# DCF77_RX_1V0.net
KiCad netlist of a schematic drawn in EAGLE
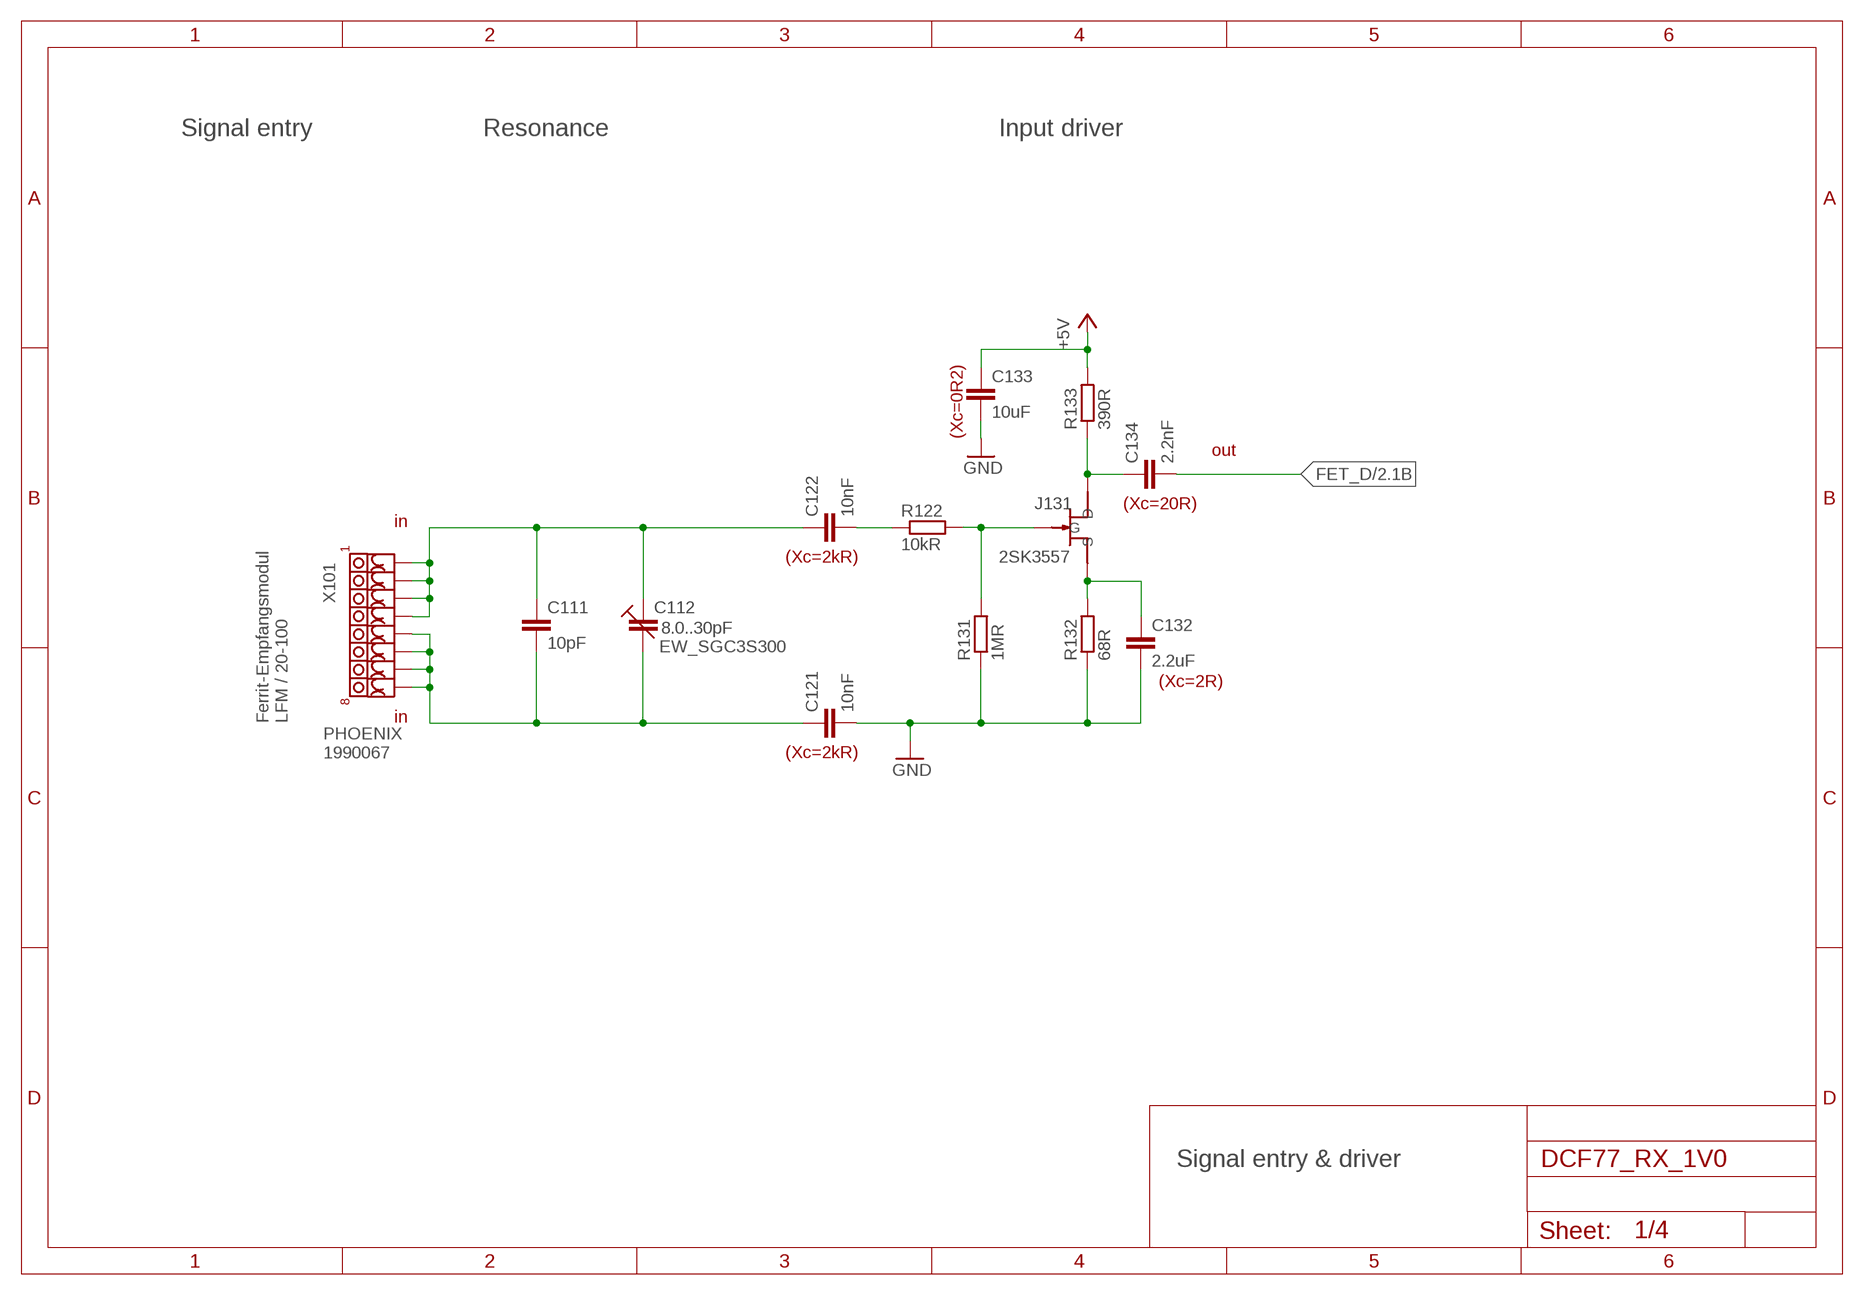
[diagram p0: schematic, sheet 1]
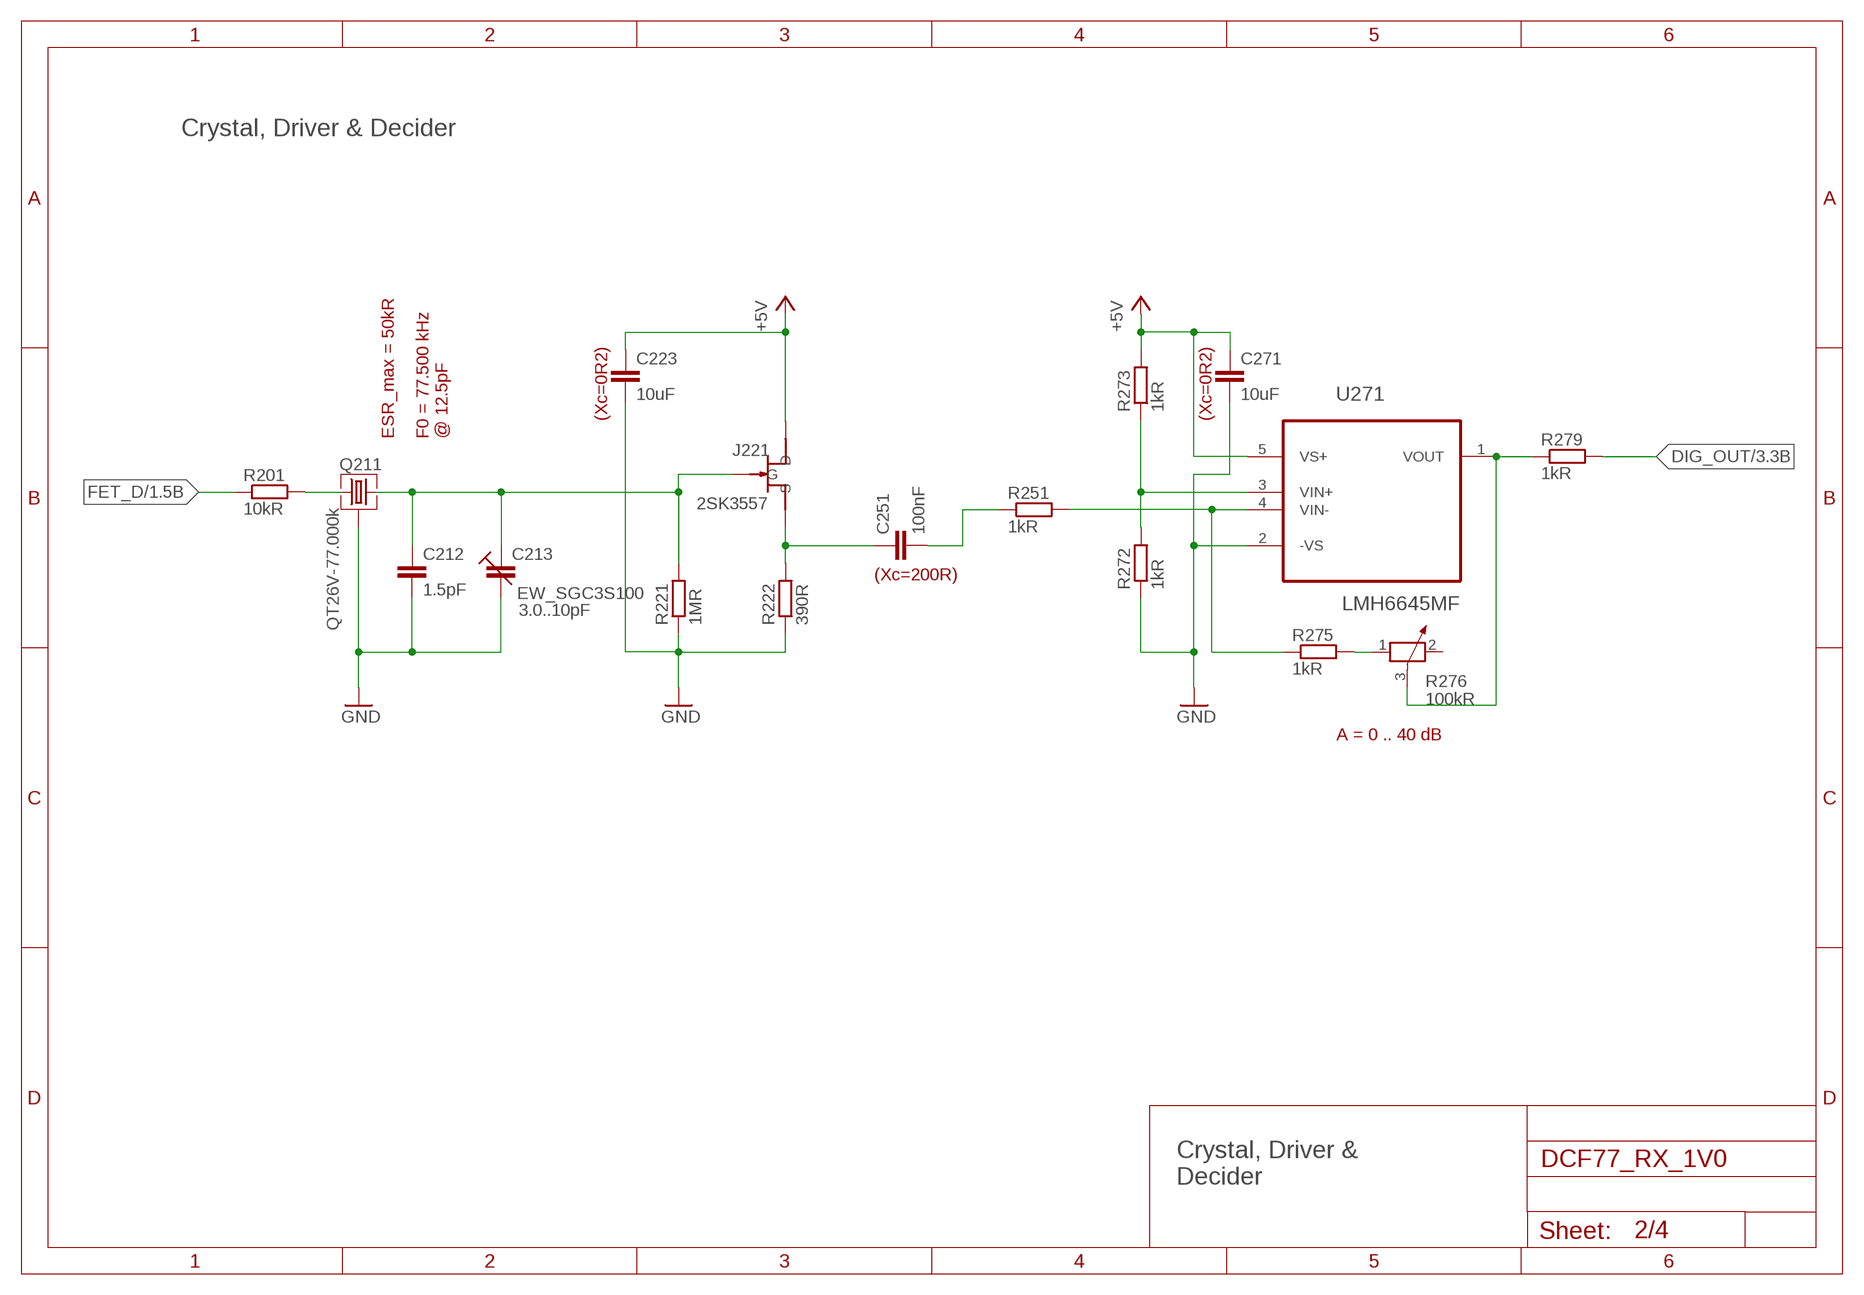
[diagram p1: schematic, sheet 2]
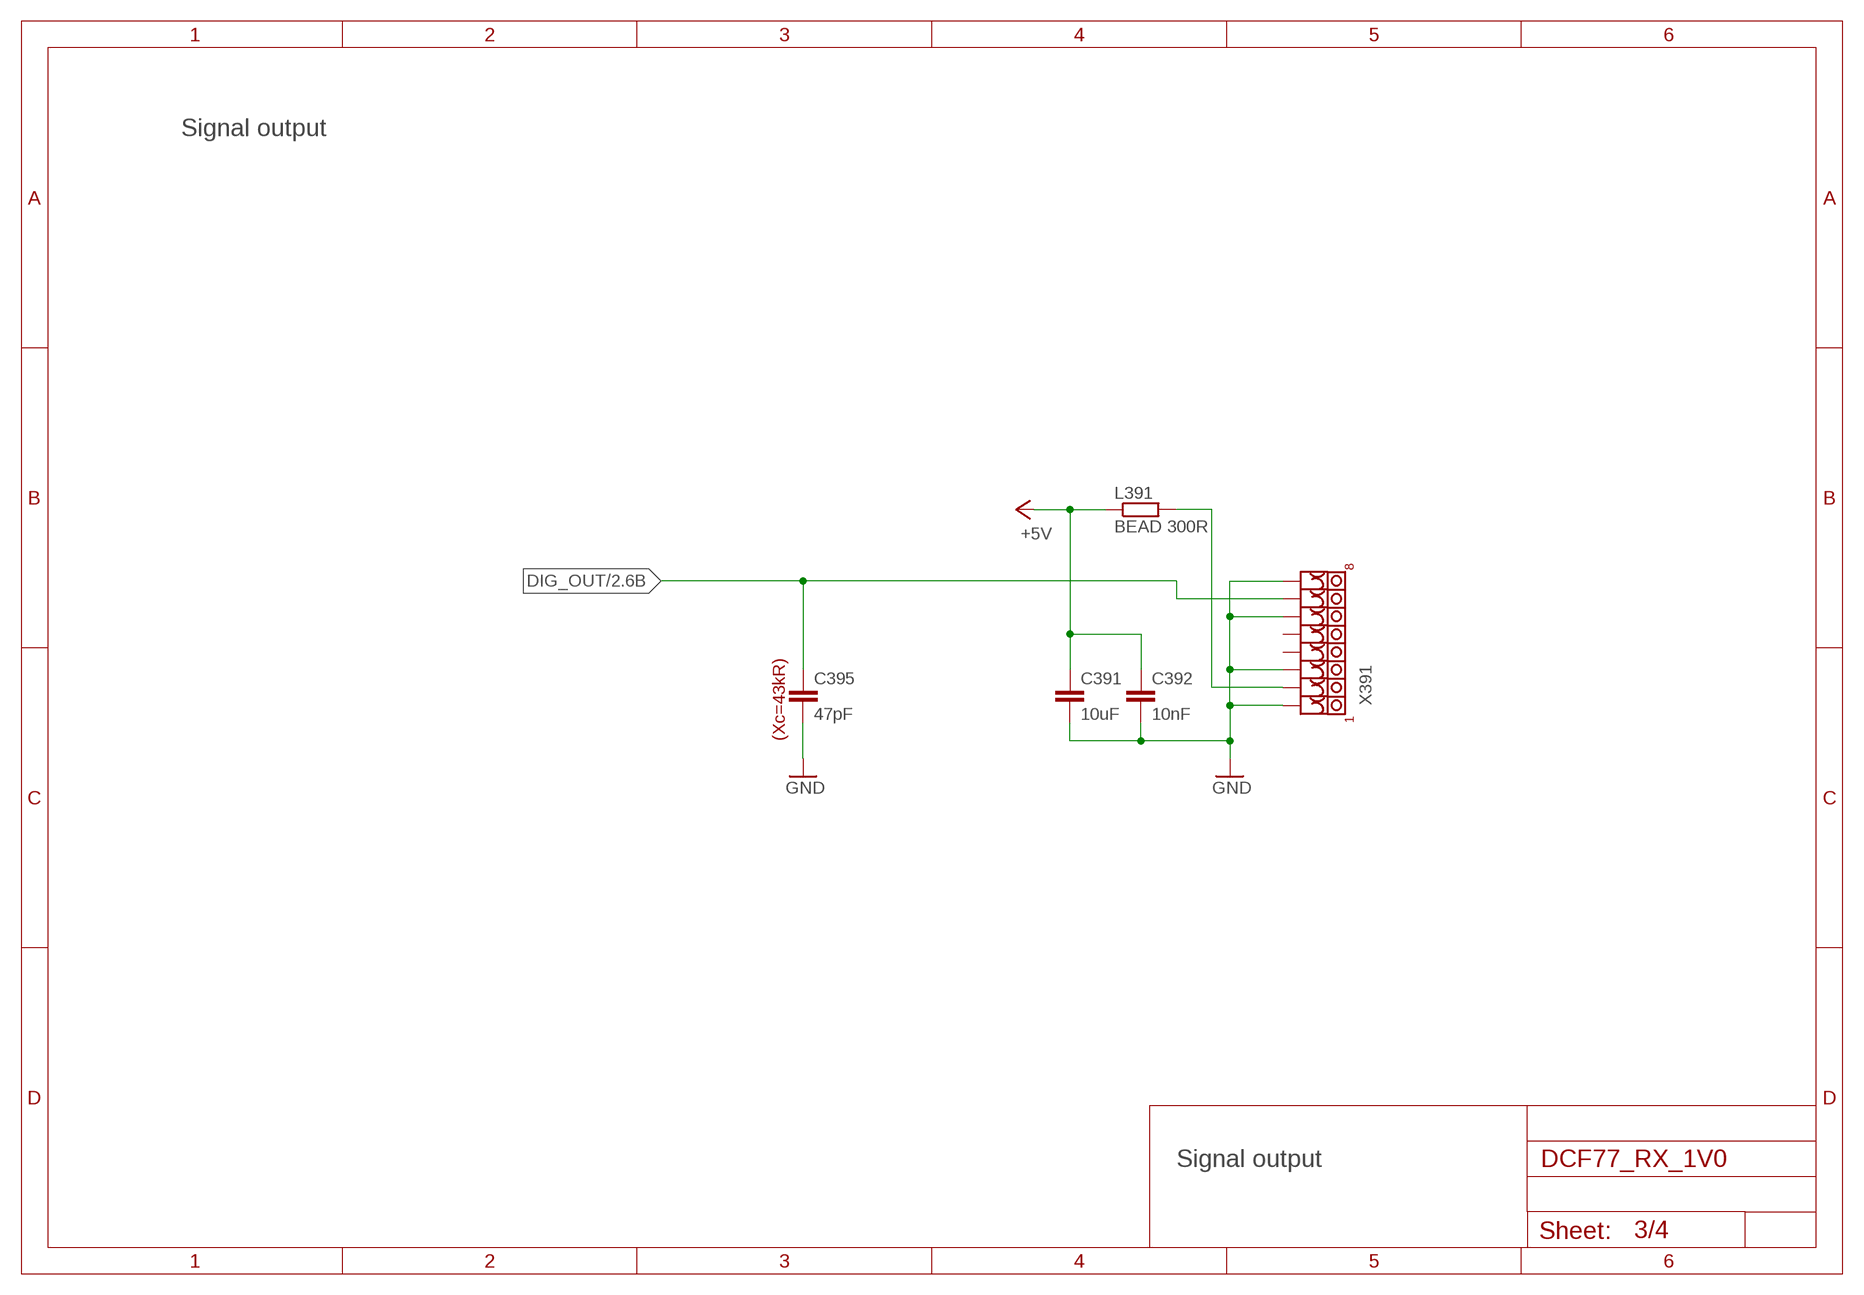
[diagram p2: schematic, sheet 3]
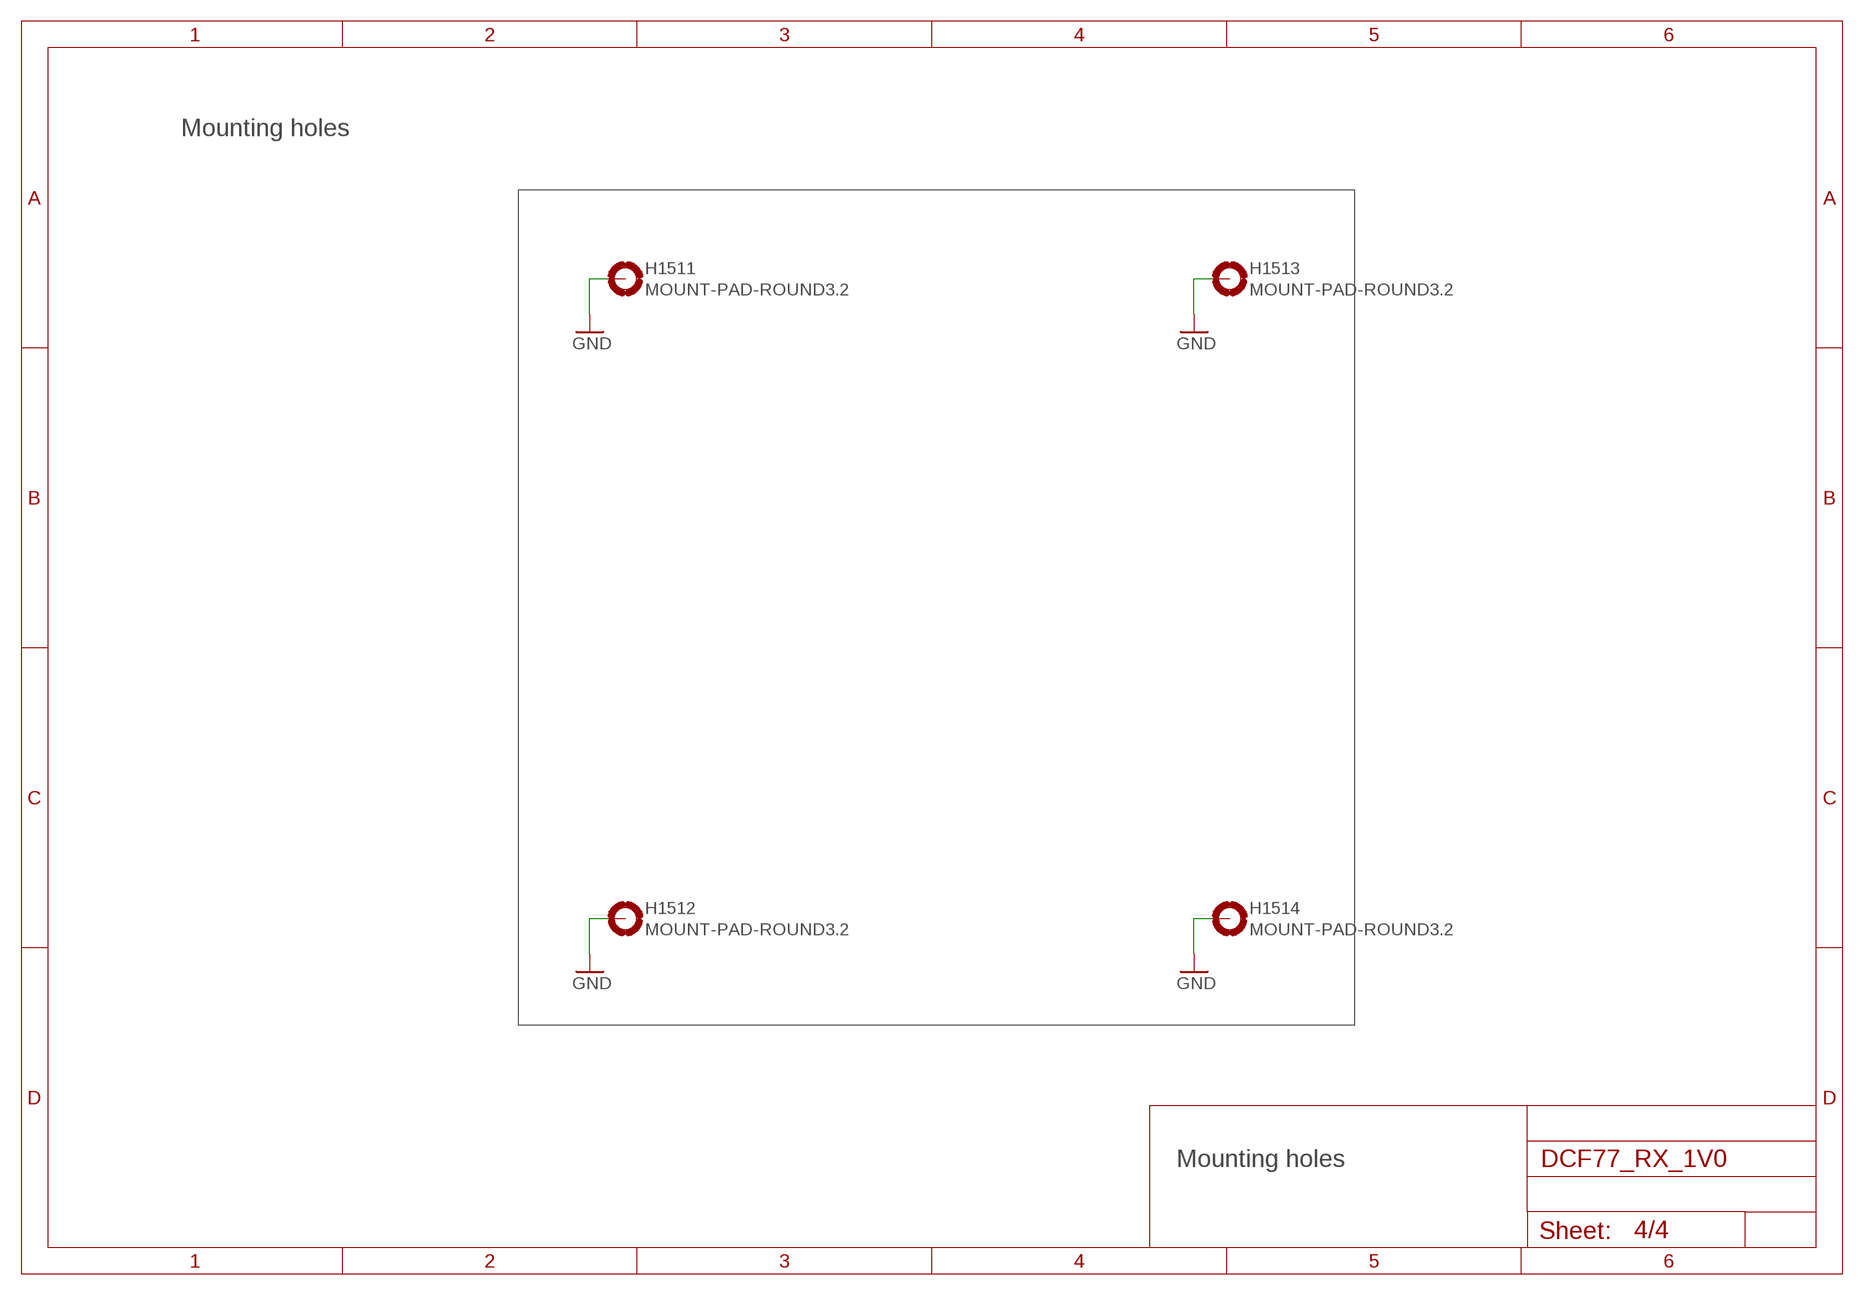
[diagram p3: schematic, sheet 4]

(export (version "E")
  (design (tool "Eeschema 10.0.6"))
  (components
    (comp (ref "C111")
      (value "10pF")
      (footprint "eagle-import:C0402")
      (libsource (lib "eagle-import") (part "C-EUC0402"))
    )
    (comp (ref "C112")
      (value "EW_SGC3S300")
      (footprint "eagle-import:4MM5_X_3MM2__EW_SGC3S")
      (libsource (lib "eagle-import") (part "C-TRIMM__EW_SGC3S"))
    )
    (comp (ref "C121")
      (value "10nF")
      (footprint "eagle-import:C0805")
      (libsource (lib "eagle-import") (part "C-EUC0805"))
    )
    (comp (ref "C122")
      (value "10nF")
      (footprint "eagle-import:C0805")
      (libsource (lib "eagle-import") (part "C-EUC0805"))
    )
    (comp (ref "C132")
      (value "2.2uF")
      (footprint "eagle-import:C0805")
      (libsource (lib "eagle-import") (part "C-EUC0805"))
    )
    (comp (ref "C133")
      (value "10uF")
      (footprint "eagle-import:C0805")
      (libsource (lib "eagle-import") (part "C-EUC0805"))
    )
    (comp (ref "C134")
      (value "2.2nF")
      (footprint "eagle-import:C0805")
      (libsource (lib "eagle-import") (part "C-EUC0805"))
    )
    (comp (ref "J131")
      (value "2SK3557")
      (footprint "eagle-import:SOT23-3")
      (libsource (lib "eagle-import") (part "2SK3557_N-JFET"))
    )
    (comp (ref "R122")
      (value "10kR")
      (footprint "eagle-import:R0805")
      (libsource (lib "eagle-import") (part "R-EU_R0805"))
    )
    (comp (ref "R131")
      (value "1MR")
      (footprint "eagle-import:R0805")
      (libsource (lib "eagle-import") (part "R-EU_R0805"))
    )
    (comp (ref "R132")
      (value "68R")
      (footprint "eagle-import:R0805")
      (libsource (lib "eagle-import") (part "R-EU_R0805"))
    )
    (comp (ref "R133")
      (value "390R")
      (footprint "eagle-import:R0805")
      (libsource (lib "eagle-import") (part "R-EU_R0805"))
    )
    (comp (ref "X101")
      (value "PHOENIX_1990067_1X8X2MM50_PTSA-0-5")
      (footprint "eagle-import:PHOENIX_1990067_1X8X2MM50_PTSA-0-5")
      (libsource (lib "eagle-import") (part "PHOENIX_1990067_1X8X2MM50_PTSA-0-5"))
    )
    (comp (ref "H1511")
      (value "MOUNT-PAD-ROUND3.2")
      (footprint "eagle-import:3,2-PAD")
      (libsource (lib "eagle-import") (part "MOUNT-PAD-ROUND3.2"))
    )
    (comp (ref "H1512")
      (value "MOUNT-PAD-ROUND3.2")
      (footprint "eagle-import:3,2-PAD")
      (libsource (lib "eagle-import") (part "MOUNT-PAD-ROUND3.2"))
    )
    (comp (ref "H1513")
      (value "MOUNT-PAD-ROUND3.2")
      (footprint "eagle-import:3,2-PAD")
      (libsource (lib "eagle-import") (part "MOUNT-PAD-ROUND3.2"))
    )
    (comp (ref "H1514")
      (value "MOUNT-PAD-ROUND3.2")
      (footprint "eagle-import:3,2-PAD")
      (libsource (lib "eagle-import") (part "MOUNT-PAD-ROUND3.2"))
    )
    (comp (ref "C391")
      (value "10uF")
      (footprint "eagle-import:C0805")
      (libsource (lib "eagle-import") (part "C-EUC0805"))
    )
    (comp (ref "C392")
      (value "10nF")
      (footprint "eagle-import:C0805")
      (libsource (lib "eagle-import") (part "C-EUC0805"))
    )
    (comp (ref "C395")
      (value "47pF")
      (footprint "eagle-import:C0805")
      (libsource (lib "eagle-import") (part "C-EUC0805"))
    )
    (comp (ref "L391")
      (value "BEAD 300R")
      (footprint "eagle-import:R1206")
      (libsource (lib "eagle-import") (part "R-EU_R1206"))
    )
    (comp (ref "X391")
      (value "PHOENIX_1990067_1X8X2MM50_PTSA-0-5")
      (footprint "eagle-import:PHOENIX_1990067_1X8X2MM50_PTSA-0-5")
      (libsource (lib "eagle-import") (part "PHOENIX_1990067_1X8X2MM50_PTSA-0-5"))
    )
    (comp (ref "C212")
      (value "1.5pF")
      (footprint "eagle-import:C0402")
      (libsource (lib "eagle-import") (part "C-EUC0402"))
    )
    (comp (ref "C213")
      (value "EW_SGC3S100")
      (footprint "eagle-import:4MM5_X_3MM2__EW_SGC3S")
      (libsource (lib "eagle-import") (part "C-TRIMM__EW_SGC3S"))
    )
    (comp (ref "C223")
      (value "10uF")
      (footprint "eagle-import:C0805")
      (libsource (lib "eagle-import") (part "C-EUC0805"))
    )
    (comp (ref "C251")
      (value "100nF")
      (footprint "eagle-import:C0805")
      (libsource (lib "eagle-import") (part "C-EUC0805"))
    )
    (comp (ref "C271")
      (value "10uF")
      (footprint "eagle-import:C0805")
      (libsource (lib "eagle-import") (part "C-EUC0805"))
    )
    (comp (ref "J221")
      (value "2SK3557")
      (footprint "eagle-import:SOT23-3")
      (libsource (lib "eagle-import") (part "2SK3557_N-JFET"))
    )
    (comp (ref "Q211")
      (value "QT26V-77.000k")
      (footprint "eagle-import:QT26V_QST")
      (libsource (lib "eagle-import") (part "QST_QT26V_77.5KHZ"))
    )
    (comp (ref "R201")
      (value "10kR")
      (footprint "eagle-import:R0805")
      (libsource (lib "eagle-import") (part "R-EU_R0805"))
    )
    (comp (ref "R221")
      (value "1MR")
      (footprint "eagle-import:R0805")
      (libsource (lib "eagle-import") (part "R-EU_R0805"))
    )
    (comp (ref "R222")
      (value "390R")
      (footprint "eagle-import:R0805")
      (libsource (lib "eagle-import") (part "R-EU_R0805"))
    )
    (comp (ref "R251")
      (value "1kR")
      (footprint "eagle-import:R0805")
      (libsource (lib "eagle-import") (part "R-EU_R0805"))
    )
    (comp (ref "R272")
      (value "1kR")
      (footprint "eagle-import:R0805")
      (libsource (lib "eagle-import") (part "R-EU_R0805"))
    )
    (comp (ref "R273")
      (value "1kR")
      (footprint "eagle-import:R0805")
      (libsource (lib "eagle-import") (part "R-EU_R0805"))
    )
    (comp (ref "R275")
      (value "1kR")
      (footprint "eagle-import:R0805")
      (libsource (lib "eagle-import") (part "R-EU_R0805"))
    )
    (comp (ref "R276")
      (value "100kR")
      (footprint "eagle-import:PT-10")
      (libsource (lib "eagle-import") (part "POTENTIOMETER_PT-10"))
    )
    (comp (ref "R279")
      (value "1kR")
      (footprint "eagle-import:R0805")
      (libsource (lib "eagle-import") (part "R-EU_R0805"))
    )
    (comp (ref "U271")
      (value "LMH6645MF")
      (footprint "eagle-import:SOT-23-5")
      (libsource (lib "eagle-import") (part "LMH6645MF"))
    )
  )
  (nets
    (net (code "1") (name "+5V") (class "Default")
      (node (ref "C133") (pin "1") (pinfunction "1_1") (pintype "passive"))
      (node (ref "C223") (pin "1") (pinfunction "1_1") (pintype "passive"))
      (node (ref "C271") (pin "1") (pinfunction "1_1") (pintype "passive"))
      (node (ref "C391") (pin "1") (pinfunction "1_1") (pintype "passive"))
      (node (ref "C392") (pin "1") (pinfunction "1_1") (pintype "passive"))
      (node (ref "J221") (pin "P$2") (pinfunction "D_P$2") (pintype "passive"))
      (node (ref "L391") (pin "1") (pinfunction "1_1") (pintype "passive"))
      (node (ref "R133") (pin "2") (pinfunction "2_2") (pintype "passive"))
      (node (ref "R273") (pin "2") (pinfunction "2_2") (pintype "passive"))
      (node (ref "U271") (pin "5") (pinfunction "VS+_5") (pintype "power_in"))
    )
    (net (code "2") (name "DIG_OUT") (class "Default")
      (node (ref "C395") (pin "1") (pinfunction "1_1") (pintype "passive"))
      (node (ref "R279") (pin "2") (pinfunction "2_2") (pintype "passive"))
      (node (ref "X391") (pin "7") (pinfunction "7_7") (pintype "passive"))
    )
    (net (code "3") (name "FET_D") (class "Default")
      (node (ref "C134") (pin "2") (pinfunction "2_2") (pintype "passive"))
      (node (ref "R201") (pin "1") (pinfunction "1_1") (pintype "passive"))
    )
    (net (code "4") (name "GND") (class "Default")
      (node (ref "C121") (pin "2") (pinfunction "2_2") (pintype "passive"))
      (node (ref "C132") (pin "2") (pinfunction "2_2") (pintype "passive"))
      (node (ref "C133") (pin "2") (pinfunction "2_2") (pintype "passive"))
      (node (ref "C212") (pin "2") (pinfunction "2_2") (pintype "passive"))
      (node (ref "C213") (pin "CSTAT") (pinfunction "CSTAT_CSTAT") (pintype "passive"))
      (node (ref "C223") (pin "2") (pinfunction "2_2") (pintype "passive"))
      (node (ref "C271") (pin "2") (pinfunction "2_2") (pintype "passive"))
      (node (ref "C391") (pin "2") (pinfunction "2_2") (pintype "passive"))
      (node (ref "C392") (pin "2") (pinfunction "2_2") (pintype "passive"))
      (node (ref "C395") (pin "2") (pinfunction "2_2") (pintype "passive"))
      (node (ref "H1511") (pin "B3,2") (pinfunction "MOUNT_B3,2") (pintype "passive"))
      (node (ref "H1512") (pin "B3,2") (pinfunction "MOUNT_B3,2") (pintype "passive"))
      (node (ref "H1513") (pin "B3,2") (pinfunction "MOUNT_B3,2") (pintype "passive"))
      (node (ref "H1514") (pin "B3,2") (pinfunction "MOUNT_B3,2") (pintype "passive"))
      (node (ref "Q211") (pin "3") (pinfunction "3_3") (pintype "passive"))
      (node (ref "Q211") (pin "4") (pinfunction "3_4") (pintype "passive"))
      (node (ref "R131") (pin "1") (pinfunction "1_1") (pintype "passive"))
      (node (ref "R132") (pin "1") (pinfunction "1_1") (pintype "passive"))
      (node (ref "R221") (pin "1") (pinfunction "1_1") (pintype "passive"))
      (node (ref "R222") (pin "1") (pinfunction "1_1") (pintype "passive"))
      (node (ref "R272") (pin "1") (pinfunction "1_1") (pintype "passive"))
      (node (ref "U271") (pin "2") (pinfunction "-VS_2") (pintype "power_in"))
      (node (ref "X391") (pin "1") (pinfunction "1_1") (pintype "passive"))
      (node (ref "X391") (pin "3") (pinfunction "3_3") (pintype "passive"))
      (node (ref "X391") (pin "6") (pinfunction "6_6") (pintype "passive"))
      (node (ref "X391") (pin "8") (pinfunction "8_8") (pintype "passive"))
    )
    (net (code "5") (name "Net-(C111-Pad1)") (class "Default")
      (node (ref "C111") (pin "1") (pinfunction "1_1") (pintype "passive"))
      (node (ref "C112") (pin "CROT") (pinfunction "CROT_CROT") (pintype "passive"))
      (node (ref "C122") (pin "1") (pinfunction "1_1") (pintype "passive"))
      (node (ref "X101") (pin "1") (pinfunction "1_1") (pintype "passive"))
      (node (ref "X101") (pin "2") (pinfunction "2_2") (pintype "passive"))
      (node (ref "X101") (pin "3") (pinfunction "3_3") (pintype "passive"))
      (node (ref "X101") (pin "4") (pinfunction "4_4") (pintype "passive"))
    )
    (net (code "6") (name "Net-(C111-Pad2)") (class "Default")
      (node (ref "C111") (pin "2") (pinfunction "2_2") (pintype "passive"))
      (node (ref "C112") (pin "CSTAT") (pinfunction "CSTAT_CSTAT") (pintype "passive"))
      (node (ref "C121") (pin "1") (pinfunction "1_1") (pintype "passive"))
      (node (ref "X101") (pin "5") (pinfunction "5_5") (pintype "passive"))
      (node (ref "X101") (pin "6") (pinfunction "6_6") (pintype "passive"))
      (node (ref "X101") (pin "7") (pinfunction "7_7") (pintype "passive"))
      (node (ref "X101") (pin "8") (pinfunction "8_8") (pintype "passive"))
    )
    (net (code "7") (name "Net-(C122-Pad2)") (class "Default")
      (node (ref "C122") (pin "2") (pinfunction "2_2") (pintype "passive"))
      (node (ref "R122") (pin "1") (pinfunction "1_1") (pintype "passive"))
    )
    (net (code "8") (name "Net-(C251-Pad2)") (class "Default")
      (node (ref "C251") (pin "2") (pinfunction "2_2") (pintype "passive"))
      (node (ref "R251") (pin "1") (pinfunction "1_1") (pintype "passive"))
    )
    (net (code "9") (name "Net-(J131-D)") (class "Default")
      (node (ref "C134") (pin "1") (pinfunction "1_1") (pintype "passive"))
      (node (ref "J131") (pin "P$2") (pinfunction "D_P$2") (pintype "passive"))
      (node (ref "R133") (pin "1") (pinfunction "1_1") (pintype "passive"))
    )
    (net (code "10") (name "Net-(J131-G)") (class "Default")
      (node (ref "J131") (pin "P$3") (pinfunction "G_P$3") (pintype "passive"))
      (node (ref "R122") (pin "2") (pinfunction "2_2") (pintype "passive"))
      (node (ref "R131") (pin "2") (pinfunction "2_2") (pintype "passive"))
    )
    (net (code "11") (name "Net-(J131-S)") (class "Default")
      (node (ref "C132") (pin "1") (pinfunction "1_1") (pintype "passive"))
      (node (ref "J131") (pin "P$1") (pinfunction "S_P$1") (pintype "passive"))
      (node (ref "R132") (pin "2") (pinfunction "2_2") (pintype "passive"))
    )
    (net (code "12") (name "Net-(J221-G)") (class "Default")
      (node (ref "C212") (pin "1") (pinfunction "1_1") (pintype "passive"))
      (node (ref "C213") (pin "CROT") (pinfunction "CROT_CROT") (pintype "passive"))
      (node (ref "J221") (pin "P$3") (pinfunction "G_P$3") (pintype "passive"))
      (node (ref "Q211") (pin "2") (pinfunction "2_2") (pintype "passive"))
      (node (ref "R221") (pin "2") (pinfunction "2_2") (pintype "passive"))
    )
    (net (code "13") (name "Net-(J221-S)") (class "Default")
      (node (ref "C251") (pin "1") (pinfunction "1_1") (pintype "passive"))
      (node (ref "J221") (pin "P$1") (pinfunction "S_P$1") (pintype "passive"))
      (node (ref "R222") (pin "2") (pinfunction "2_2") (pintype "passive"))
    )
    (net (code "14") (name "Net-(L391-Pad2)") (class "Default")
      (node (ref "L391") (pin "2") (pinfunction "2_2") (pintype "passive"))
      (node (ref "X391") (pin "2") (pinfunction "2_2") (pintype "passive"))
    )
    (net (code "15") (name "Net-(Q211-Pad1)") (class "Default")
      (node (ref "Q211") (pin "1") (pinfunction "1_1") (pintype "passive"))
      (node (ref "R201") (pin "2") (pinfunction "2_2") (pintype "passive"))
    )
    (net (code "16") (name "Net-(R275-Pad2)") (class "Default")
      (node (ref "R275") (pin "2") (pinfunction "2_2") (pintype "passive"))
      (node (ref "R276") (pin "1") (pinfunction "1_1") (pintype "passive"))
    )
    (net (code "17") (name "Net-(U271-VIN+)") (class "Default")
      (node (ref "R272") (pin "2") (pinfunction "2_2") (pintype "passive"))
      (node (ref "R273") (pin "1") (pinfunction "1_1") (pintype "passive"))
      (node (ref "U271") (pin "3") (pinfunction "VIN+_3") (pintype "input"))
    )
    (net (code "18") (name "Net-(U271-VIN-)") (class "Default")
      (node (ref "R251") (pin "2") (pinfunction "2_2") (pintype "passive"))
      (node (ref "R275") (pin "1") (pinfunction "1_1") (pintype "passive"))
      (node (ref "U271") (pin "4") (pinfunction "VIN-_4") (pintype "input"))
    )
    (net (code "19") (name "Net-(U271-VOUT)") (class "Default")
      (node (ref "R276") (pin "3") (pinfunction "3_3") (pintype "passive"))
      (node (ref "R279") (pin "1") (pinfunction "1_1") (pintype "passive"))
      (node (ref "U271") (pin "1") (pinfunction "VOUT_1") (pintype "output"))
    )
    (net (code "20") (name "unconnected-(R276-Pad2)") (class "Default")
      (node (ref "R276") (pin "2") (pinfunction "2_2") (pintype "passive"))
    )
    (net (code "21") (name "unconnected-(X391-Pad4)") (class "Default")
      (node (ref "X391") (pin "4") (pinfunction "4_4") (pintype "passive"))
    )
    (net (code "22") (name "unconnected-(X391-Pad5)") (class "Default")
      (node (ref "X391") (pin "5") (pinfunction "5_5") (pintype "passive"))
    )
  )
)
